# Sheet1.net
KiCad netlist of a schematic drawn in Altium Designer
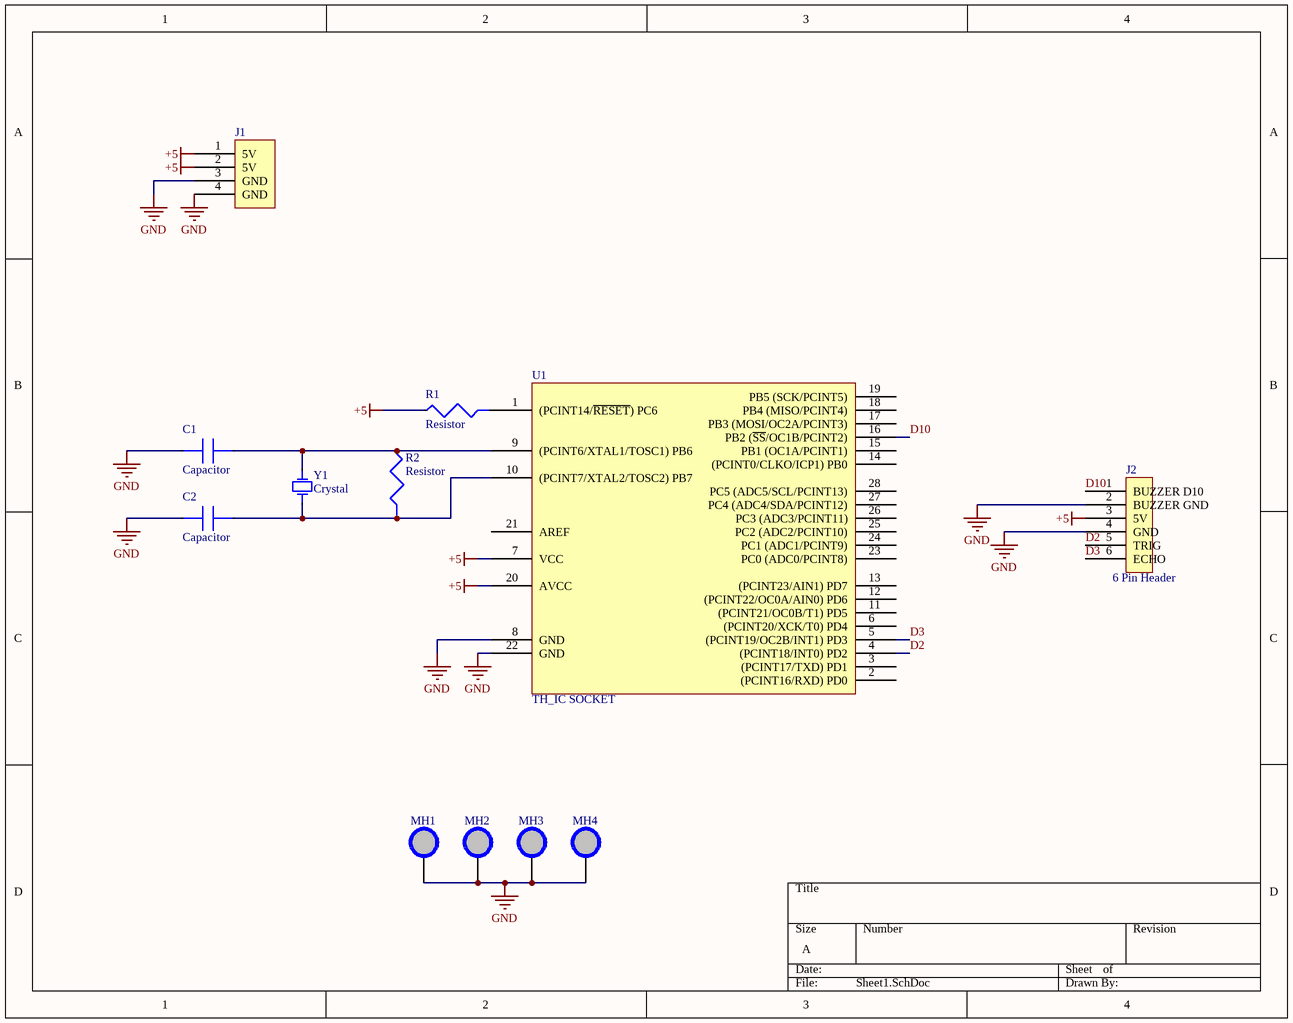
[diagram p0: Sheet1.SchDoc]

(export (version "E")
  (design (tool "Eeschema 10.0.6"))
  (components
    (comp (ref "C1")
      (value "Capacitor")
      (footprint "Capacitor TH")
      (libsource (lib "Schlib1") (part "Capacitor"))
    )
    (comp (ref "C2")
      (value "Capacitor")
      (footprint "Capacitor TH")
      (libsource (lib "Schlib1") (part "Capacitor"))
    )
    (comp (ref "J1")
      (value "4 Pin Header, 1 Row, Female, 2.54mm Pitch")
      (footprint "4 Pin Header")
      (fields (field (name "MANUFACTURER") "Harwin") (field (name "MANUFACTURER PART NUMBER") "M20-7820446"))
      (libsource (lib "Schlib1") (part "M20-7820446"))
    )
    (comp (ref "J2")
      (value "6 Pin Header")
      (footprint "6 PIN HEADER")
      (description "6 Pin Header Board Connector")
      (fields (field (name "MANUFACTURER") "3M") (field (name "MANUFACTURER PART NUMBER") "929850-01-06-RB"))
      (libsource (lib "Schlib1") (part "929850-01-06-RB"))
    )
    (comp (ref "MH1")
      (value "Mounting Hole")
      (footprint "Mounting Hole")
      (libsource (lib "Schlib1") (part "Mounting Hole"))
    )
    (comp (ref "MH2")
      (value "Mounting Hole")
      (footprint "Mounting Hole")
      (libsource (lib "Schlib1") (part "Mounting Hole"))
    )
    (comp (ref "MH3")
      (value "Mounting Hole")
      (footprint "Mounting Hole")
      (libsource (lib "Schlib1") (part "Mounting Hole"))
    )
    (comp (ref "MH4")
      (value "Mounting Hole")
      (footprint "Mounting Hole")
      (libsource (lib "Schlib1") (part "Mounting Hole"))
    )
    (comp (ref "R1") (value "Resistor") (footprint "Resistor") (libsource (lib "Schlib1") (part "Resistor")))
    (comp (ref "R2") (value "Resistor") (footprint "Resistor") (libsource (lib "Schlib1") (part "Resistor")))
    (comp (ref "U1")
      (value "TH_IC SOCKET")
      (footprint "28dip_through_hole_ic_socket")
      (description "Through Hole IC Sockets 28P / .300\"")
      (fields
        (field (name "MANUFACTURER") "Adam Equipment")
        (field (name "MANUFACTURER PART NUMBER") "ICS-328-T")
      )
      (libsource (lib "Schlib1") (part "ICS-328-T"))
    )
    (comp (ref "Y1") (value "Crystal") (footprint "Crystal") (libsource (lib "Schlib1") (part "Crystal")))
  )
  (nets
    (net (code "1") (name "+5") (class "Default")
      (node (ref "J1") (pin "1") (pinfunction "5V_1") (pintype "passive"))
      (node (ref "J1") (pin "2") (pinfunction "5V_2") (pintype "passive"))
      (node (ref "J2") (pin "3") (pinfunction "5V_3") (pintype "passive"))
      (node (ref "R1") (pin "2") (pinfunction "2_2") (pintype "passive"))
      (node (ref "U1") (pin "20") (pinfunction "AVCC_20") (pintype "passive"))
      (node (ref "U1") (pin "7") (pinfunction "VCC_7") (pintype "passive"))
    )
    (net (code "2") (name "/D2") (class "Default")
      (node (ref "J2") (pin "5") (pinfunction "TRIG_5") (pintype "passive"))
      (node (ref "U1") (pin "4") (pinfunction "(PCINT18/INT0)_PD2_4") (pintype "passive"))
    )
    (net (code "3") (name "/D3") (class "Default")
      (node (ref "J2") (pin "6") (pinfunction "ECHO_6") (pintype "passive"))
      (node (ref "U1") (pin "5") (pinfunction "(PCINT19/OC2B/INT1)_PD3_5") (pintype "passive"))
    )
    (net (code "4") (name "/D10") (class "Default")
      (node (ref "J2") (pin "1") (pinfunction "BUZZER_D10_1") (pintype "passive"))
      (node (ref "U1") (pin "16") (pinfunction "PB2_(~{SS}/OC1B/PCINT2)_16") (pintype "passive"))
    )
    (net (code "5") (name "GND") (class "Default")
      (node (ref "C1") (pin "1") (pinfunction "1_1") (pintype "passive"))
      (node (ref "C2") (pin "1") (pinfunction "1_1") (pintype "passive"))
      (node (ref "J1") (pin "3") (pinfunction "GND_3") (pintype "passive"))
      (node (ref "J1") (pin "4") (pinfunction "GND_4") (pintype "passive"))
      (node (ref "J2") (pin "2") (pinfunction "BUZZER_GND_2") (pintype "passive"))
      (node (ref "J2") (pin "4") (pinfunction "GND_4") (pintype "passive"))
      (node (ref "MH1") (pin "1") (pinfunction "1_1") (pintype "passive"))
      (node (ref "MH2") (pin "1") (pinfunction "1_1") (pintype "passive"))
      (node (ref "MH3") (pin "1") (pinfunction "1_1") (pintype "passive"))
      (node (ref "MH4") (pin "1") (pinfunction "1_1") (pintype "passive"))
      (node (ref "U1") (pin "22") (pinfunction "GND_22") (pintype "passive"))
      (node (ref "U1") (pin "8") (pinfunction "GND_8") (pintype "passive"))
    )
    (net (code "6") (name "Net-(U1-(PCINT6{slash}XTAL1{slash}TOSC1)_PB6)") (class "Default")
      (node (ref "C1") (pin "2") (pinfunction "2_2") (pintype "passive"))
      (node (ref "R2") (pin "2") (pinfunction "2_2") (pintype "passive"))
      (node (ref "U1") (pin "9") (pinfunction "(PCINT6/XTAL1/TOSC1)_PB6_9") (pintype "passive"))
      (node (ref "Y1") (pin "1") (pinfunction "1_1") (pintype "passive"))
    )
    (net (code "7") (name "Net-(U1-(PCINT7{slash}XTAL2{slash}TOSC2)_PB7)") (class "Default")
      (node (ref "C2") (pin "2") (pinfunction "2_2") (pintype "passive"))
      (node (ref "R2") (pin "1") (pinfunction "1_1") (pintype "passive"))
      (node (ref "U1") (pin "10") (pinfunction "(PCINT7/XTAL2/TOSC2)_PB7_10") (pintype "passive"))
      (node (ref "Y1") (pin "2") (pinfunction "2_2") (pintype "passive"))
    )
    (net (code "8") (name "Net-(U1-(PCINT14{slash}~{RESET})_PC6)") (class "Default")
      (node (ref "R1") (pin "1") (pinfunction "1_1") (pintype "passive"))
      (node (ref "U1") (pin "1") (pinfunction "(PCINT14/~{RESET})_PC6_1") (pintype "passive"))
    )
    (net (code "9") (name "unconnected-(U1-(PCINT0{slash}CLKO{slash}ICP1)_PB0-Pad14)") (class "Default")
      (node (ref "U1") (pin "14") (pinfunction "(PCINT0/CLKO/ICP1)_PB0_14") (pintype "passive"))
    )
    (net (code "10") (name "unconnected-(U1-(PCINT16{slash}RXD)_PD0-Pad2)") (class "Default")
      (node (ref "U1") (pin "2") (pinfunction "(PCINT16/RXD)_PD0_2") (pintype "passive"))
    )
    (net (code "11") (name "unconnected-(U1-(PCINT17{slash}TXD)_PD1-Pad3)") (class "Default")
      (node (ref "U1") (pin "3") (pinfunction "(PCINT17/TXD)_PD1_3") (pintype "passive"))
    )
    (net (code "12") (name "unconnected-(U1-(PCINT20{slash}XCK{slash}T0)_PD4-Pad6)") (class "Default")
      (node (ref "U1") (pin "6") (pinfunction "(PCINT20/XCK/T0)_PD4_6") (pintype "passive"))
    )
    (net (code "13") (name "unconnected-(U1-(PCINT21{slash}OC0B{slash}T1)_PD5-Pad11)") (class "Default")
      (node (ref "U1") (pin "11") (pinfunction "(PCINT21/OC0B/T1)_PD5_11") (pintype "passive"))
    )
    (net (code "14") (name "unconnected-(U1-(PCINT22{slash}OC0A{slash}AIN0)_PD6-Pad12)") (class "Default")
      (node (ref "U1") (pin "12") (pinfunction "(PCINT22/OC0A/AIN0)_PD6_12") (pintype "passive"))
    )
    (net (code "15") (name "unconnected-(U1-(PCINT23{slash}AIN1)_PD7-Pad13)") (class "Default")
      (node (ref "U1") (pin "13") (pinfunction "(PCINT23/AIN1)_PD7_13") (pintype "passive"))
    )
    (net (code "16") (name "unconnected-(U1-AREF-Pad21)") (class "Default")
      (node (ref "U1") (pin "21") (pinfunction "AREF_21") (pintype "passive"))
    )
    (net (code "17") (name "unconnected-(U1-PB1_(OC1A{slash}PCINT1)-Pad15)") (class "Default")
      (node (ref "U1") (pin "15") (pinfunction "PB1_(OC1A/PCINT1)_15") (pintype "passive"))
    )
    (net (code "18") (name "unconnected-(U1-PB3_(MOSI{slash}OC2A{slash}PCINT3)-Pad17)") (class "Default")
      (node (ref "U1") (pin "17") (pinfunction "PB3_(MOSI/OC2A/PCINT3)_17") (pintype "passive"))
    )
    (net (code "19") (name "unconnected-(U1-PB4_(MISO{slash}PCINT4)-Pad18)") (class "Default")
      (node (ref "U1") (pin "18") (pinfunction "PB4_(MISO/PCINT4)_18") (pintype "passive"))
    )
    (net (code "20") (name "unconnected-(U1-PB5_(SCK{slash}PCINT5)-Pad19)") (class "Default")
      (node (ref "U1") (pin "19") (pinfunction "PB5_(SCK/PCINT5)_19") (pintype "passive"))
    )
    (net (code "21") (name "unconnected-(U1-PC0_(ADC0{slash}PCINT8)-Pad23)") (class "Default")
      (node (ref "U1") (pin "23") (pinfunction "PC0_(ADC0/PCINT8)_23") (pintype "passive"))
    )
    (net (code "22") (name "unconnected-(U1-PC1_(ADC1{slash}PCINT9)-Pad24)") (class "Default")
      (node (ref "U1") (pin "24") (pinfunction "PC1_(ADC1/PCINT9)_24") (pintype "passive"))
    )
    (net (code "23") (name "unconnected-(U1-PC2_(ADC2{slash}PCINT10)-Pad25)") (class "Default")
      (node (ref "U1") (pin "25") (pinfunction "PC2_(ADC2/PCINT10)_25") (pintype "passive"))
    )
    (net (code "24") (name "unconnected-(U1-PC3_(ADC3{slash}PCINT11)-Pad26)") (class "Default")
      (node (ref "U1") (pin "26") (pinfunction "PC3_(ADC3/PCINT11)_26") (pintype "passive"))
    )
    (net (code "25") (name "unconnected-(U1-PC4_(ADC4{slash}SDA{slash}PCINT12)-Pad27)") (class "Default")
      (node (ref "U1") (pin "27") (pinfunction "PC4_(ADC4/SDA/PCINT12)_27") (pintype "passive"))
    )
    (net (code "26") (name "unconnected-(U1-PC5_(ADC5{slash}SCL{slash}PCINT13)-Pad28)") (class "Default")
      (node (ref "U1") (pin "28") (pinfunction "PC5_(ADC5/SCL/PCINT13)_28") (pintype "passive"))
    )
  )
)
